# SERIALIO.net
KiCad netlist of a schematic drawn in Altium Designer
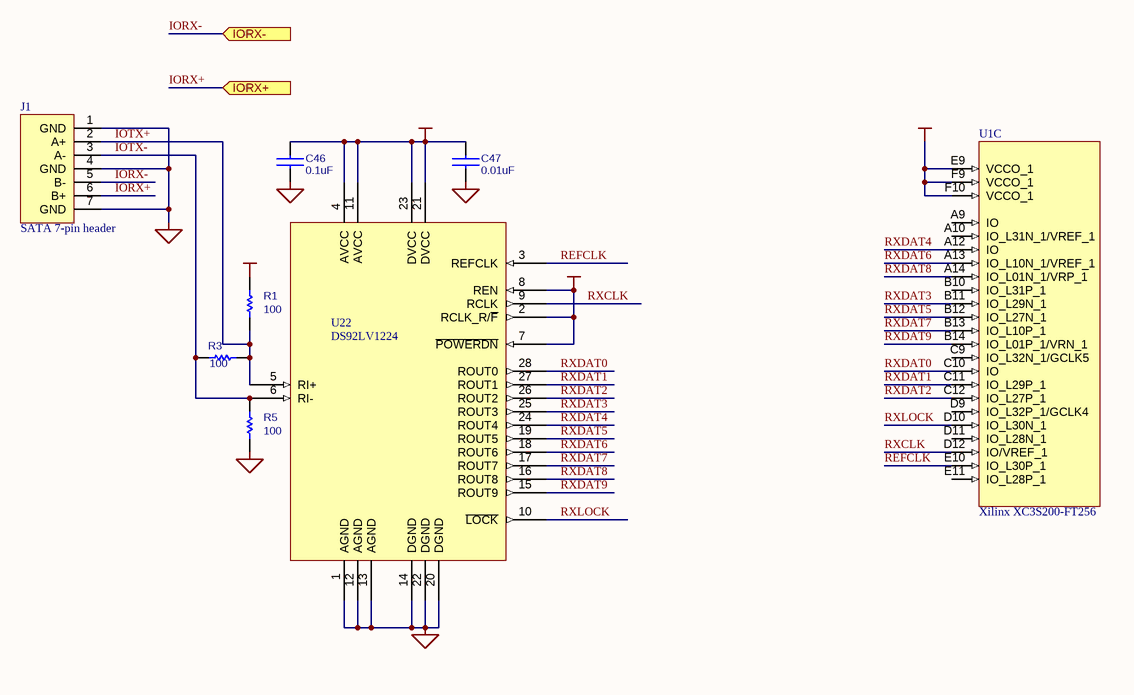
[diagram p0: SERIALIO.SCHDOC]

(export (version "E")
  (design (tool "Eeschema 10.0.6"))
  (components
    (comp (ref "C46")
      (value "0.1uF")
      (footprint "0603")
      (description "Standard Capacitor")
      (fields (field (name "Comment") "CAPACITOR"))
      (libsource (lib "parts") (part "CAPACITOR"))
    )
    (comp (ref "C47")
      (value "0.01uF")
      (footprint "0402")
      (description "Standard Capacitor")
      (fields (field (name "Comment") "CAPACITOR"))
      (libsource (lib "parts") (part "CAPACITOR"))
    )
    (comp (ref "J1")
      (value "SATA 7-pin header")
      (footprint "MOLES 67800-5005")
      (libsource (lib "parts") (part "SATA-7"))
    )
    (comp (ref "R1")
      (value "100")
      (footprint "0603")
      (description "Standard Passive Resistor")
      (libsource (lib "parts") (part "RESISTOR"))
    )
    (comp (ref "R3")
      (value "100")
      (footprint "0603")
      (description "Standard Passive Resistor")
      (libsource (lib "parts") (part "RESISTOR"))
    )
    (comp (ref "R5")
      (value "100")
      (footprint "0603")
      (description "Standard Passive Resistor")
      (libsource (lib "parts") (part "RESISTOR"))
    )
    (comp (ref "U1")
      (value "Xilinx XC3S200-FT256")
      (footprint "Xilinx FT256 BGA")
      (description "Xilinx Spartan-3 FPGA")
      (libsource (lib "parts") (part "XC3S200-FT256"))
    )
    (comp (ref "U22")
      (value "DS92LV1224")
      (footprint "SSO-G28/E4.3")
      (description "30-66 MHz 10-Bit Bus LVDS Deserializer")
      (libsource (lib "parts") (part "DS92LV1224"))
    )
  )
  (nets
    (net (code "1") (name "/IORX+") (class "Default")
      (node (ref "J1") (pin "6") (pinfunction "B+_6") (pintype "passive"))
    )
    (net (code "2") (name "/IORX-") (class "Default")
      (node (ref "J1") (pin "5") (pinfunction "B-_5") (pintype "passive"))
    )
    (net (code "3") (name "/IOTX+") (class "Default")
      (node (ref "J1") (pin "2") (pinfunction "A+_2") (pintype "passive"))
      (node (ref "R1") (pin "2") (pintype "passive"))
      (node (ref "R3") (pin "2") (pintype "passive"))
      (node (ref "U22") (pin "5") (pinfunction "RI+_5") (pintype "input"))
    )
    (net (code "4") (name "/IOTX-") (class "Default")
      (node (ref "J1") (pin "3") (pinfunction "A-_3") (pintype "passive"))
      (node (ref "R3") (pin "1") (pintype "passive"))
      (node (ref "R5") (pin "2") (pintype "passive"))
      (node (ref "U22") (pin "6") (pinfunction "RI-_6") (pintype "input"))
    )
    (net (code "5") (name "/REFCLK") (class "Default")
      (node (ref "U1") (pin "E10") (pinfunction "IO_L30P_1_E10") (pintype "input"))
      (node (ref "U22") (pin "3") (pinfunction "REFCLK_3") (pintype "input"))
    )
    (net (code "6") (name "/RXCLK") (class "Default")
      (node (ref "U1") (pin "D12") (pinfunction "IO/VREF_1_D12") (pintype "input"))
      (node (ref "U22") (pin "9") (pinfunction "RCLK_9") (pintype "output"))
    )
    (net (code "7") (name "/RXDAT0") (class "Default")
      (node (ref "U1") (pin "C10") (pinfunction "IO_C10") (pintype "input"))
      (node (ref "U22") (pin "28") (pinfunction "ROUT0_28") (pintype "output"))
    )
    (net (code "8") (name "/RXDAT1") (class "Default")
      (node (ref "U1") (pin "C11") (pinfunction "IO_L29P_1_C11") (pintype "input"))
      (node (ref "U22") (pin "27") (pinfunction "ROUT1_27") (pintype "output"))
    )
    (net (code "9") (name "/RXDAT2") (class "Default")
      (node (ref "U1") (pin "C12") (pinfunction "IO_L27P_1_C12") (pintype "input"))
      (node (ref "U22") (pin "26") (pinfunction "ROUT2_26") (pintype "output"))
    )
    (net (code "10") (name "/RXDAT3") (class "Default")
      (node (ref "U1") (pin "B11") (pinfunction "IO_L29N_1_B11") (pintype "input"))
      (node (ref "U22") (pin "25") (pinfunction "ROUT3_25") (pintype "output"))
    )
    (net (code "11") (name "/RXDAT4") (class "Default")
      (node (ref "U1") (pin "A12") (pinfunction "IO_A12") (pintype "input"))
      (node (ref "U22") (pin "24") (pinfunction "ROUT4_24") (pintype "output"))
    )
    (net (code "12") (name "/RXDAT5") (class "Default")
      (node (ref "U1") (pin "B12") (pinfunction "IO_L27N_1_B12") (pintype "input"))
      (node (ref "U22") (pin "19") (pinfunction "ROUT5_19") (pintype "output"))
    )
    (net (code "13") (name "/RXDAT6") (class "Default")
      (node (ref "U1") (pin "A13") (pinfunction "IO_L10N_1/VREF_1_A13") (pintype "input"))
      (node (ref "U22") (pin "18") (pinfunction "ROUT6_18") (pintype "output"))
    )
    (net (code "14") (name "/RXDAT7") (class "Default")
      (node (ref "U1") (pin "B13") (pinfunction "IO_L10P_1_B13") (pintype "input"))
      (node (ref "U22") (pin "17") (pinfunction "ROUT7_17") (pintype "output"))
    )
    (net (code "15") (name "/RXDAT8") (class "Default")
      (node (ref "U1") (pin "A14") (pinfunction "IO_L01N_1/VRP_1_A14") (pintype "input"))
      (node (ref "U22") (pin "16") (pinfunction "ROUT8_16") (pintype "output"))
    )
    (net (code "16") (name "/RXDAT9") (class "Default")
      (node (ref "U1") (pin "B14") (pinfunction "IO_L01P_1/VRN_1_B14") (pintype "input"))
      (node (ref "U22") (pin "15") (pinfunction "ROUT9_15") (pintype "output"))
    )
    (net (code "17") (name "/RXLOCK") (class "Default")
      (node (ref "U1") (pin "D10") (pinfunction "IO_L30N_1_D10") (pintype "input"))
      (node (ref "U22") (pin "10") (pinfunction "~{LOCK}_10") (pintype "output"))
    )
    (net (code "18") (name "GND") (class "Default")
      (node (ref "C46") (pin "1") (pintype "passive"))
      (node (ref "C47") (pin "1") (pintype "passive"))
      (node (ref "J1") (pin "1") (pinfunction "GND_1") (pintype "passive"))
      (node (ref "J1") (pin "4") (pinfunction "GND_4") (pintype "passive"))
      (node (ref "J1") (pin "7") (pinfunction "GND_7") (pintype "passive"))
      (node (ref "R5") (pin "1") (pintype "passive"))
      (node (ref "U22") (pin "1") (pinfunction "AGND_1") (pintype "power_in"))
      (node (ref "U22") (pin "12") (pinfunction "AGND_12") (pintype "power_in"))
      (node (ref "U22") (pin "13") (pinfunction "AGND_13") (pintype "power_in"))
      (node (ref "U22") (pin "14") (pinfunction "DGND_14") (pintype "power_in"))
      (node (ref "U22") (pin "20") (pinfunction "DGND_20") (pintype "power_in"))
      (node (ref "U22") (pin "22") (pinfunction "DGND_22") (pintype "power_in"))
    )
    (net (code "19") (name "VCC") (class "Default")
      (node (ref "C46") (pin "2") (pintype "passive"))
      (node (ref "C47") (pin "2") (pintype "passive"))
      (node (ref "R1") (pin "1") (pintype "passive"))
      (node (ref "U1") (pin "E9") (pinfunction "VCCO_1_E9") (pintype "input"))
      (node (ref "U1") (pin "F10") (pinfunction "VCCO_1_F10") (pintype "input"))
      (node (ref "U1") (pin "F9") (pinfunction "VCCO_1_F9") (pintype "input"))
      (node (ref "U22") (pin "11") (pinfunction "AVCC_11") (pintype "power_in"))
      (node (ref "U22") (pin "2") (pinfunction "RCLK_R/~{F}_2") (pintype "output"))
      (node (ref "U22") (pin "21") (pinfunction "DVCC_21") (pintype "power_in"))
      (node (ref "U22") (pin "23") (pinfunction "DVCC_23") (pintype "power_in"))
      (node (ref "U22") (pin "4") (pinfunction "AVCC_4") (pintype "power_in"))
      (node (ref "U22") (pin "7") (pinfunction "~{POWERDN}_7") (pintype "input"))
      (node (ref "U22") (pin "8") (pinfunction "REN_8") (pintype "input"))
    )
    (net (code "20") (name "unconnected-(U1C-IO-PadA9)") (class "Default")
      (node (ref "U1") (pin "A9") (pinfunction "IO_A9") (pintype "input"))
    )
    (net (code "21") (name "unconnected-(U1C-IO_L28N_1-PadD11)") (class "Default")
      (node (ref "U1") (pin "D11") (pinfunction "IO_L28N_1_D11") (pintype "input"))
    )
    (net (code "22") (name "unconnected-(U1C-IO_L28P_1-PadE11)") (class "Default")
      (node (ref "U1") (pin "E11") (pinfunction "IO_L28P_1_E11") (pintype "input"))
    )
    (net (code "23") (name "unconnected-(U1C-IO_L31N_1{slash}VREF_1-PadA10)") (class "Default")
      (node (ref "U1") (pin "A10") (pinfunction "IO_L31N_1/VREF_1_A10") (pintype "input"))
    )
    (net (code "24") (name "unconnected-(U1C-IO_L31P_1-PadB10)") (class "Default")
      (node (ref "U1") (pin "B10") (pinfunction "IO_L31P_1_B10") (pintype "input"))
    )
    (net (code "25") (name "unconnected-(U1C-IO_L32N_1{slash}GCLK5-PadC9)") (class "Default")
      (node (ref "U1") (pin "C9") (pinfunction "IO_L32N_1/GCLK5_C9") (pintype "input"))
    )
    (net (code "26") (name "unconnected-(U1C-IO_L32P_1{slash}GCLK4-PadD9)") (class "Default")
      (node (ref "U1") (pin "D9") (pinfunction "IO_L32P_1/GCLK4_D9") (pintype "input"))
    )
  )
)
